# og1_0.net
KiCad netlist of a schematic drawn in EAGLE
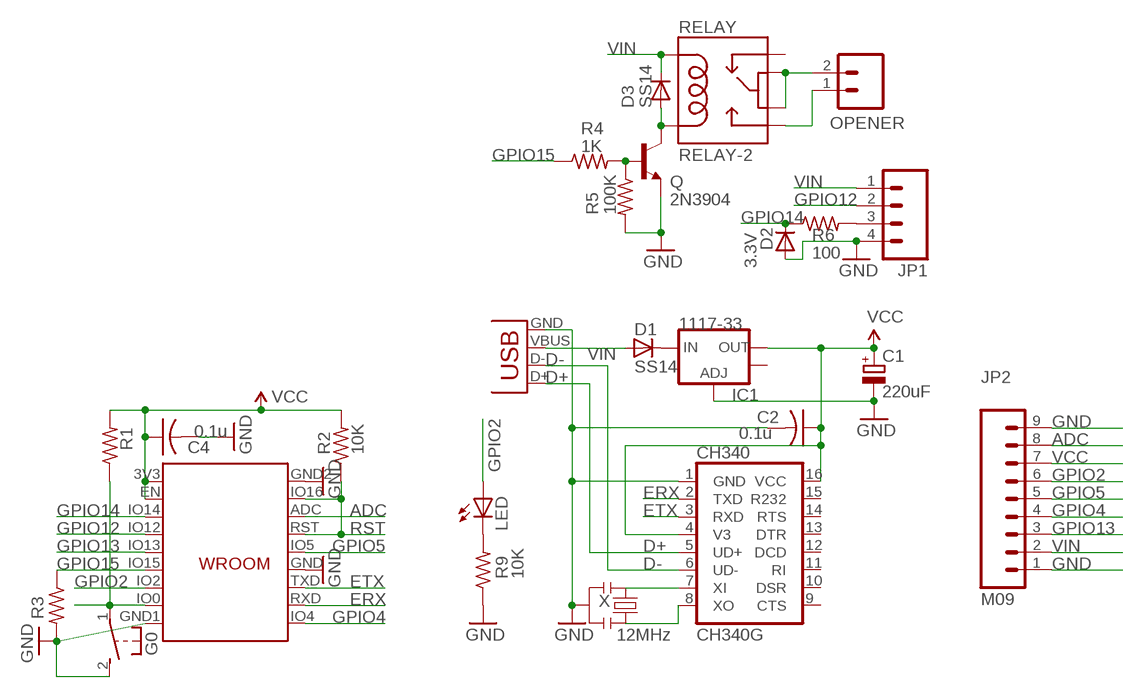
[diagram p0: schematic, sheet 1]

(export (version "E")
  (design (tool "Eeschema 10.0.6"))
  (components
    (comp (ref "C1")
      (value "220uF")
      (footprint "eagle-import:CT3528")
      (libsource (lib "eagle-import") (part "CPOL-EUCT3528"))
    )
    (comp (ref "C2")
      (value "0.1u")
      (footprint "eagle-import:C0603K")
      (libsource (lib "eagle-import") (part "C-USC0603K"))
    )
    (comp (ref "C4")
      (value "0.1u")
      (footprint "eagle-import:C0603K")
      (libsource (lib "eagle-import") (part "C-USC0603K"))
    )
    (comp (ref "CH340")
      (value "CH340G")
      (footprint "eagle-import:SO16")
      (libsource (lib "eagle-import") (part "CH340G"))
    )
    (comp (ref "D1")
      (value "SS14")
      (footprint "eagle-import:DO-214AC")
      (libsource (lib "eagle-import") (part "DIODE-DO-214AC"))
    )
    (comp (ref "D2")
      (value "3.3V")
      (footprint "eagle-import:MINIMELF")
      (libsource (lib "eagle-import") (part "DIODE-MINIMELF"))
    )
    (comp (ref "D3")
      (value "SS14")
      (footprint "eagle-import:DO-214AC")
      (libsource (lib "eagle-import") (part "DIODE-DO-214AC"))
    )
    (comp (ref "ESP")
      (value "WROOM02")
      (footprint "eagle-import:WROOM")
      (libsource (lib "eagle-import") (part "WROOM02"))
    )
    (comp (ref "G0")
      (value "31-XX")
      (footprint "eagle-import:B3F-31XX")
      (libsource (lib "eagle-import") (part "31-XX"))
    )
    (comp (ref "IC1")
      (value "1117-33")
      (footprint "eagle-import:SOT223")
      (libsource (lib "eagle-import") (part "V_REG_LM1117SOT223"))
    )
    (comp (ref "JP1")
      (value "M04SONIC")
      (footprint "eagle-import:1X04_SONICSENSOR")
      (libsource (lib "eagle-import") (part "M04SONIC"))
    )
    (comp (ref "JP2")
      (value "M09")
      (footprint "eagle-import:1X09")
      (libsource (lib "eagle-import") (part "M09"))
    )
    (comp (ref "LED")
      (value "LEDLED3MM_ABBRV")
      (footprint "eagle-import:LED3MM_ABBRV")
      (libsource (lib "eagle-import") (part "LEDLED3MM_ABBRV"))
    )
    (comp (ref "OPENER")
      (value "OPENER")
      (footprint "eagle-import:SCREWTERMINAL-4MM-2-X")
      (libsource (lib "eagle-import") (part "M024MM-X"))
    )
    (comp (ref "Q")
      (value "2N3904")
      (footprint "eagle-import:SOT23-3")
      (libsource (lib "eagle-import") (part "TRANSISTOR_NPNSOT23-3"))
    )
    (comp (ref "R1")
      (value "10K")
      (footprint "eagle-import:R0603")
      (libsource (lib "eagle-import") (part "R-US_R0603"))
    )
    (comp (ref "R2")
      (value "10K")
      (footprint "eagle-import:R0603")
      (libsource (lib "eagle-import") (part "R-US_R0603"))
    )
    (comp (ref "R3")
      (value "10K")
      (footprint "eagle-import:R0603")
      (libsource (lib "eagle-import") (part "R-US_R0603"))
    )
    (comp (ref "R4")
      (value "1K")
      (footprint "eagle-import:R0603")
      (libsource (lib "eagle-import") (part "adafruit2013_R-US_R0603"))
    )
    (comp (ref "R5")
      (value "100K")
      (footprint "eagle-import:R0603")
      (libsource (lib "eagle-import") (part "adafruit2013_R-US_R0603"))
    )
    (comp (ref "R6")
      (value "100")
      (footprint "eagle-import:R0603")
      (libsource (lib "eagle-import") (part "adafruit2013_R-US_R0603"))
    )
    (comp (ref "R9")
      (value "10K")
      (footprint "eagle-import:R0603")
      (libsource (lib "eagle-import") (part "R-US_R0603"))
    )
    (comp (ref "RELAY")
      (value "RELAY-2")
      (footprint "eagle-import:RELAY-HK4100F")
      (libsource (lib "eagle-import") (part "RELAY-2"))
    )
    (comp (ref "X")
      (value "12MHz")
      (footprint "eagle-import:RESONATOR-SMD")
      (libsource (lib "eagle-import") (part "RESONATORSMD"))
    )
    (comp (ref "X3")
      (value "USB-MICROB")
      (footprint "eagle-import:USB-MICROB")
      (libsource (lib "eagle-import") (part "USB-MICROB"))
    )
  )
  (nets
    (net (code "1") (name "/ADC") (class "Default")
      (node (ref "ESP") (pin "ADC") (pinfunction "ADC_ADC") (pintype "bidirectional"))
      (node (ref "JP2") (pin "8") (pinfunction "8_8") (pintype "passive"))
    )
    (net (code "2") (name "/D+") (class "Default")
      (node (ref "CH340") (pin "5") (pinfunction "UD+_5") (pintype "bidirectional"))
      (node (ref "X3") (pin "D+") (pinfunction "D+_D+") (pintype "bidirectional"))
    )
    (net (code "3") (name "/D-") (class "Default")
      (node (ref "CH340") (pin "6") (pinfunction "UD-_6") (pintype "bidirectional"))
      (node (ref "X3") (pin "D-") (pinfunction "D-_D-") (pintype "bidirectional"))
    )
    (net (code "4") (name "/ERX") (class "Default")
      (node (ref "CH340") (pin "2") (pinfunction "TXD_2") (pintype "bidirectional"))
      (node (ref "ESP") (pin "RXD") (pinfunction "RX_RXD") (pintype "bidirectional"))
    )
    (net (code "5") (name "/ETX") (class "Default")
      (node (ref "CH340") (pin "3") (pinfunction "RXD_3") (pintype "bidirectional"))
      (node (ref "ESP") (pin "TXD") (pinfunction "TX_TXD") (pintype "bidirectional"))
    )
    (net (code "6") (name "/GPIO2") (class "Default")
      (node (ref "ESP") (pin "IO2") (pinfunction "IO2_IO2") (pintype "bidirectional"))
      (node (ref "JP2") (pin "6") (pinfunction "6_6") (pintype "passive"))
      (node (ref "LED") (pin "A") (pinfunction "A_A") (pintype "passive"))
    )
    (net (code "7") (name "/GPIO4") (class "Default")
      (node (ref "ESP") (pin "IO4") (pinfunction "IO4_IO4") (pintype "bidirectional"))
      (node (ref "JP2") (pin "4") (pinfunction "4_4") (pintype "passive"))
    )
    (net (code "8") (name "/GPIO5") (class "Default")
      (node (ref "ESP") (pin "IO5") (pinfunction "IO5_IO5") (pintype "bidirectional"))
      (node (ref "JP2") (pin "5") (pinfunction "5_5") (pintype "passive"))
    )
    (net (code "9") (name "/GPIO12") (class "Default")
      (node (ref "ESP") (pin "IO12") (pinfunction "IO12_IO12") (pintype "bidirectional"))
      (node (ref "JP1") (pin "2") (pinfunction "2_2") (pintype "passive"))
    )
    (net (code "10") (name "/GPIO13") (class "Default")
      (node (ref "ESP") (pin "IO13") (pinfunction "IO13_IO13") (pintype "bidirectional"))
      (node (ref "JP2") (pin "3") (pinfunction "3_3") (pintype "passive"))
    )
    (net (code "11") (name "/GPIO14") (class "Default")
      (node (ref "D2") (pin "C") (pinfunction "C_C") (pintype "passive"))
      (node (ref "ESP") (pin "IO14") (pinfunction "IO14_IO14") (pintype "bidirectional"))
      (node (ref "R6") (pin "1") (pinfunction "1_1") (pintype "passive"))
    )
    (net (code "12") (name "/GPIO15") (class "Default")
      (node (ref "ESP") (pin "IO15") (pinfunction "IO15_IO15") (pintype "bidirectional"))
      (node (ref "R3") (pin "1") (pinfunction "1_1") (pintype "passive"))
      (node (ref "R4") (pin "1") (pinfunction "1_1") (pintype "passive"))
    )
    (net (code "13") (name "/RST") (class "Default")
      (node (ref "ESP") (pin "IO16") (pinfunction "IO16_IO16") (pintype "bidirectional"))
      (node (ref "ESP") (pin "RST") (pinfunction "RST_RST") (pintype "bidirectional"))
      (node (ref "R2") (pin "1") (pinfunction "1_1") (pintype "passive"))
    )
    (net (code "14") (name "/VIN") (class "Default")
      (node (ref "D1") (pin "A") (pinfunction "A_A") (pintype "passive"))
      (node (ref "D3") (pin "C") (pinfunction "C_C") (pintype "passive"))
      (node (ref "JP1") (pin "1") (pinfunction "1_1") (pintype "passive"))
      (node (ref "JP2") (pin "2") (pinfunction "2_2") (pintype "passive"))
      (node (ref "RELAY") (pin "2") (pinfunction "2_2") (pintype "bidirectional"))
      (node (ref "X3") (pin "VBUS") (pinfunction "VBUS_VBUS") (pintype "bidirectional"))
    )
    (net (code "15") (name "GND") (class "Default")
      (node (ref "C1") (pin "-") (pinfunction "-_-") (pintype "passive"))
      (node (ref "C2") (pin "2") (pinfunction "2_2") (pintype "passive"))
      (node (ref "C4") (pin "2") (pinfunction "2_2") (pintype "passive"))
      (node (ref "CH340") (pin "1") (pinfunction "GND_1") (pintype "power_in"))
      (node (ref "D2") (pin "A") (pinfunction "A_A") (pintype "passive"))
      (node (ref "ESP") (pin "GND") (pinfunction "GND_GND") (pintype "power_in"))
      (node (ref "ESP") (pin "GND1") (pinfunction "GND1_GND1") (pintype "power_in"))
      (node (ref "ESP") (pin "GND2") (pinfunction "GND2_GND2") (pintype "power_in"))
      (node (ref "G0") (pin "2") (pinfunction "S_2") (pintype "passive"))
      (node (ref "IC1") (pin "1") (pinfunction "ADJ_1") (pintype "input"))
      (node (ref "JP1") (pin "4") (pinfunction "4_4") (pintype "passive"))
      (node (ref "JP2") (pin "1") (pinfunction "1_1") (pintype "passive"))
      (node (ref "JP2") (pin "9") (pinfunction "9_9") (pintype "passive"))
      (node (ref "Q") (pin "2") (pinfunction "E_2") (pintype "passive"))
      (node (ref "R3") (pin "2") (pinfunction "2_2") (pintype "passive"))
      (node (ref "R5") (pin "2") (pinfunction "2_2") (pintype "passive"))
      (node (ref "R9") (pin "1") (pinfunction "1_1") (pintype "passive"))
      (node (ref "X") (pin "2") (pinfunction "2_2") (pintype "passive"))
      (node (ref "X3") (pin "GND") (pinfunction "GND_GND") (pintype "bidirectional"))
    )
    (net (code "16") (name "Net-(CH340-XI)") (class "Default")
      (node (ref "CH340") (pin "7") (pinfunction "XI_7") (pintype "bidirectional"))
      (node (ref "X") (pin "1") (pinfunction "1_1") (pintype "passive"))
    )
    (net (code "17") (name "Net-(CH340-XO)") (class "Default")
      (node (ref "CH340") (pin "8") (pinfunction "XO_8") (pintype "bidirectional"))
      (node (ref "X") (pin "3") (pinfunction "3_3") (pintype "passive"))
    )
    (net (code "18") (name "Net-(G0-P)") (class "Default")
      (node (ref "ESP") (pin "IO0") (pinfunction "IO0_IO0") (pintype "bidirectional"))
      (node (ref "G0") (pin "1") (pinfunction "P_1") (pintype "passive"))
      (node (ref "R1") (pin "1") (pinfunction "1_1") (pintype "passive"))
    )
    (net (code "19") (name "Net-(IC1-IN)") (class "Default")
      (node (ref "D1") (pin "C") (pinfunction "C_C") (pintype "passive"))
      (node (ref "IC1") (pin "3") (pinfunction "IN_3") (pintype "input"))
    )
    (net (code "20") (name "Net-(JP1-Pad3)") (class "Default")
      (node (ref "JP1") (pin "3") (pinfunction "3_3") (pintype "passive"))
      (node (ref "R6") (pin "2") (pinfunction "2_2") (pintype "passive"))
    )
    (net (code "21") (name "Net-(LED-C)") (class "Default")
      (node (ref "LED") (pin "K") (pinfunction "C_K") (pintype "passive"))
      (node (ref "R9") (pin "2") (pinfunction "2_2") (pintype "passive"))
    )
    (net (code "22") (name "Net-(OPENER-Pad1)") (class "Default")
      (node (ref "OPENER") (pin "1") (pinfunction "1_1") (pintype "passive"))
      (node (ref "RELAY") (pin "10") (pinfunction "10_10") (pintype "bidirectional"))
    )
    (net (code "23") (name "Net-(OPENER-Pad2)") (class "Default")
      (node (ref "OPENER") (pin "2") (pinfunction "2_2") (pintype "passive"))
      (node (ref "RELAY") (pin "5") (pinfunction "5_5") (pintype "bidirectional"))
      (node (ref "RELAY") (pin "6") (pinfunction "6_6") (pintype "bidirectional"))
    )
    (net (code "24") (name "Net-(Q-B)") (class "Default")
      (node (ref "Q") (pin "1") (pinfunction "B_1") (pintype "passive"))
      (node (ref "R4") (pin "2") (pinfunction "2_2") (pintype "passive"))
      (node (ref "R5") (pin "1") (pinfunction "1_1") (pintype "passive"))
    )
    (net (code "25") (name "Net-(Q-C)") (class "Default")
      (node (ref "D3") (pin "A") (pinfunction "A_A") (pintype "passive"))
      (node (ref "Q") (pin "3") (pinfunction "C_3") (pintype "passive"))
      (node (ref "RELAY") (pin "9") (pinfunction "9_9") (pintype "bidirectional"))
    )
    (net (code "26") (name "VCC") (class "Default")
      (node (ref "C1") (pin "+") (pinfunction "+_+") (pintype "passive"))
      (node (ref "C2") (pin "1") (pinfunction "1_1") (pintype "passive"))
      (node (ref "C4") (pin "1") (pinfunction "1_1") (pintype "passive"))
      (node (ref "CH340") (pin "16") (pinfunction "VCC_16") (pintype "power_in"))
      (node (ref "CH340") (pin "4") (pinfunction "V3_4") (pintype "bidirectional"))
      (node (ref "ESP") (pin "3V3") (pinfunction "VCC_3V3") (pintype "power_in"))
      (node (ref "ESP") (pin "EN") (pinfunction "EN_EN") (pintype "bidirectional"))
      (node (ref "IC1") (pin "2") (pinfunction "OUT_2") (pintype "bidirectional"))
      (node (ref "JP2") (pin "7") (pinfunction "7_7") (pintype "passive"))
      (node (ref "R1") (pin "2") (pinfunction "2_2") (pintype "passive"))
      (node (ref "R2") (pin "2") (pinfunction "2_2") (pintype "passive"))
    )
    (net (code "27") (name "unconnected-(CH340-CTS-Pad9)") (class "Default")
      (node (ref "CH340") (pin "9") (pinfunction "CTS_9") (pintype "bidirectional"))
    )
    (net (code "28") (name "unconnected-(CH340-DCD-Pad12)") (class "Default")
      (node (ref "CH340") (pin "12") (pinfunction "DCD_12") (pintype "bidirectional"))
    )
    (net (code "29") (name "unconnected-(CH340-DSR-Pad10)") (class "Default")
      (node (ref "CH340") (pin "10") (pinfunction "DSR_10") (pintype "bidirectional"))
    )
    (net (code "30") (name "unconnected-(CH340-DTR-Pad13)") (class "Default")
      (node (ref "CH340") (pin "13") (pinfunction "DTR_13") (pintype "bidirectional"))
    )
    (net (code "31") (name "unconnected-(CH340-R232-Pad15)") (class "Default")
      (node (ref "CH340") (pin "15") (pinfunction "R232_15") (pintype "bidirectional"))
    )
    (net (code "32") (name "unconnected-(CH340-RI-Pad11)") (class "Default")
      (node (ref "CH340") (pin "11") (pinfunction "RI_11") (pintype "bidirectional"))
    )
    (net (code "33") (name "unconnected-(CH340-RTS-Pad14)") (class "Default")
      (node (ref "CH340") (pin "14") (pinfunction "RTS_14") (pintype "bidirectional"))
    )
    (net (code "34") (name "unconnected-(IC1-OUT-Pad4)") (class "Default")
      (node (ref "IC1") (pin "4") (pinfunction "OUT_4") (pintype "bidirectional"))
    )
    (net (code "35") (name "unconnected-(RELAY-Pad1)") (class "Default")
      (node (ref "RELAY") (pin "1") (pinfunction "1_1") (pintype "bidirectional"))
    )
  )
)
